# Supply_5V_to_3V3-_Ams1117.net
KiCad netlist of a schematic drawn in Altium Designer
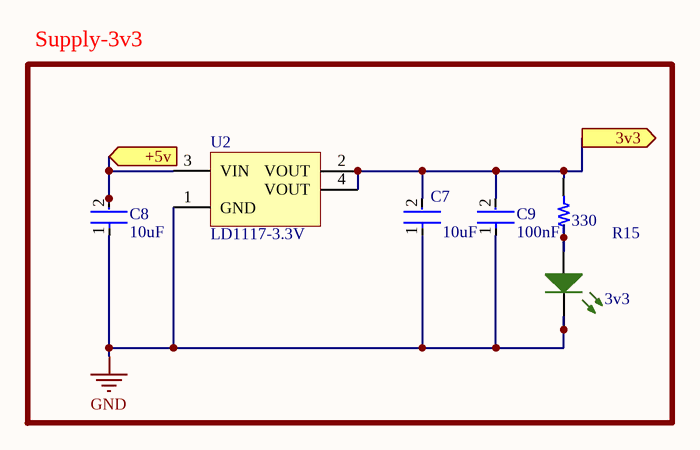
[diagram p0: Supply 5V to 3V3- Ams1117.SchDoc]

(export (version "E")
  (design (tool "Eeschema 10.0.6"))
  (components
    (comp (ref "3v3")
      (value "LED SMD 0805 GREEN")
      (footprint "LED_0805_GREEN")
      (libsource (lib "Led") (part "LED SMD 0805 GREEN"))
    )
    (comp (ref "C7")
      (value "10uF")
      (footprint "FP-C0805C-DN-MFG")
      (description "CAP CER 0.22UF 50V X7R 0805")
      (fields
        (field (name "MANUFACTURER") "KEMET")
        (field (name "OCTOPART") "https://octopart.com/c0805c224k5ractu-kemet-144670")
      )
      (libsource (lib "Altium Content Vault") (part "b4654b650e69147ec39a6b967a45e02"))
    )
    (comp (ref "C8")
      (value "10uF")
      (footprint "FP-C0805C-DN-IPC_B")
      (description "CAP CER 0.22UF 50V X7R 0805")
      (fields
        (field (name "MANUFACTURER") "KEMET")
        (field (name "OCTOPART") "https://octopart.com/c0805c224k5ractu-kemet-144670")
      )
      (libsource (lib "Altium Content Vault") (part "b4654b650e69147ec39a6b967a45e02"))
    )
    (comp (ref "C9")
      (value "100nF")
      (footprint "FP-C0805C-DN-IPC_B")
      (description "CAP CER 0.22UF 50V X7R 0805")
      (fields
        (field (name "MANUFACTURER") "KEMET")
        (field (name "OCTOPART") "https://octopart.com/c0805c224k5ractu-kemet-144670")
      )
      (libsource (lib "Altium Content Vault") (part "b4654b650e69147ec39a6b967a45e02"))
    )
    (comp (ref "R15")
      (value "330")
      (footprint "RES 0805_2012")
      (description "SMT Resistor")
      (libsource (lib "Resistor") (part "Res 0805"))
    )
    (comp (ref "U2")
      (value "LD1117-3.3V")
      (footprint "SOT-223-4 6.5X7MM P2.3MM")
      (description "Linear Voltage Regulator IC  1 Output  800mA SOT-223")
      (fields (field (name "PARTNUMBER") "LD1117S33CTR"))
      (libsource (lib "Chip") (part "LD1117-3.3V (SMD SOT-223)"))
    )
  )
  (nets
    (net (code "1") (name "/+5v") (class "Default")
      (node (ref "C8") (pin "2") (pinfunction "2_2") (pintype "passive"))
      (node (ref "U2") (pin "3") (pinfunction "VIN_3") (pintype "passive"))
    )
    (net (code "2") (name "/3v3") (class "Default")
      (node (ref "C7") (pin "2") (pinfunction "2_2") (pintype "passive"))
      (node (ref "C9") (pin "2") (pinfunction "2_2") (pintype "passive"))
      (node (ref "R15") (pin "1") (pinfunction "1_1") (pintype "passive"))
      (node (ref "U2") (pin "2") (pinfunction "VOUT_2") (pintype "passive"))
      (node (ref "U2") (pin "4") (pinfunction "VOUT_4") (pintype "passive"))
    )
    (net (code "3") (name "GND") (class "Default")
      (node (ref "3v3") (pin "2") (pinfunction "K_2") (pintype "passive"))
      (node (ref "C7") (pin "1") (pinfunction "1_1") (pintype "passive"))
      (node (ref "C8") (pin "1") (pinfunction "1_1") (pintype "passive"))
      (node (ref "C9") (pin "1") (pinfunction "1_1") (pintype "passive"))
      (node (ref "U2") (pin "1") (pinfunction "GND_1") (pintype "passive"))
    )
    (net (code "4") (name "Net-(3v3-A)") (class "Default")
      (node (ref "3v3") (pin "1") (pinfunction "A_1") (pintype "passive"))
      (node (ref "R15") (pin "2") (pinfunction "2_2") (pintype "passive"))
    )
  )
)
